# mySatellite.net
KiCad netlist of a schematic drawn in EAGLE
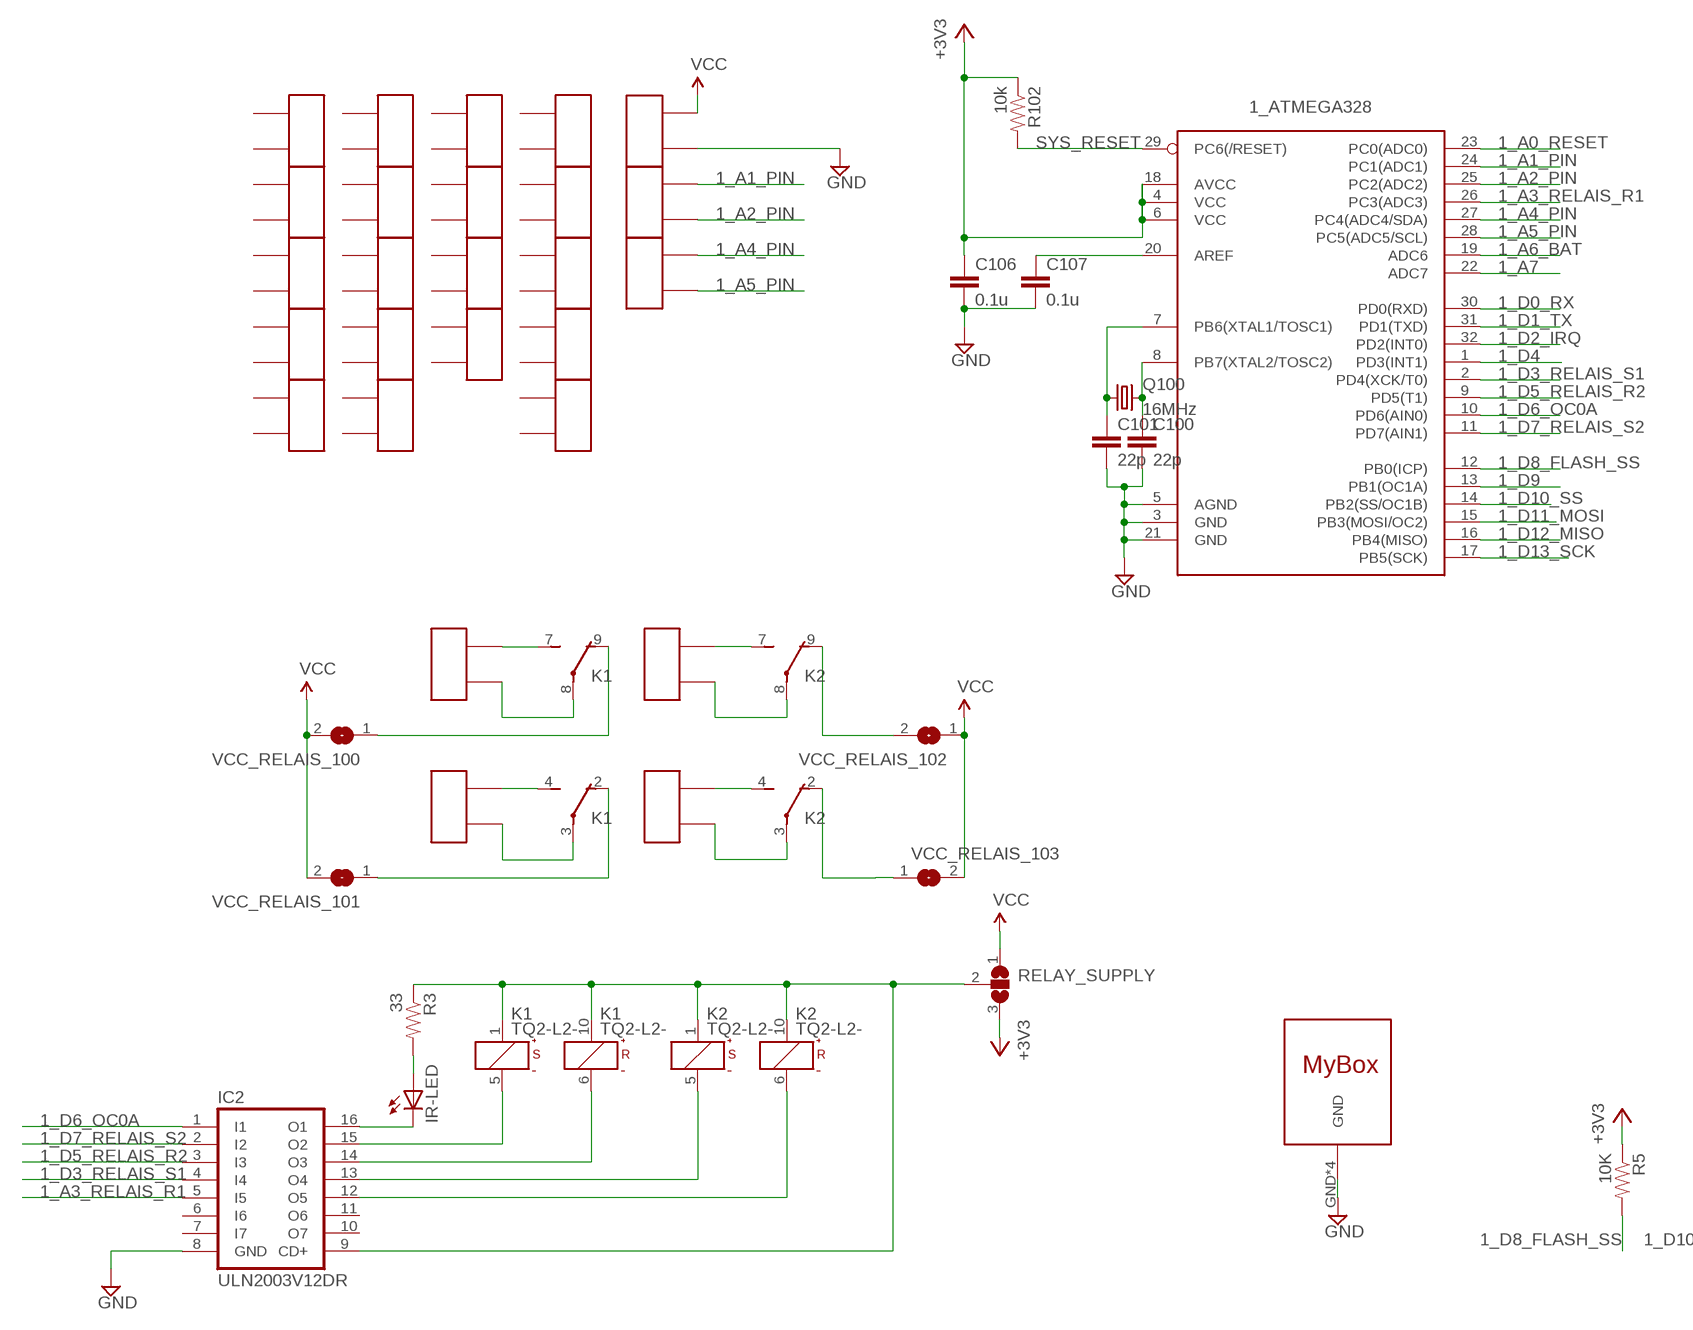
[diagram p0: schematic, sheet 1, part 1 of 2]
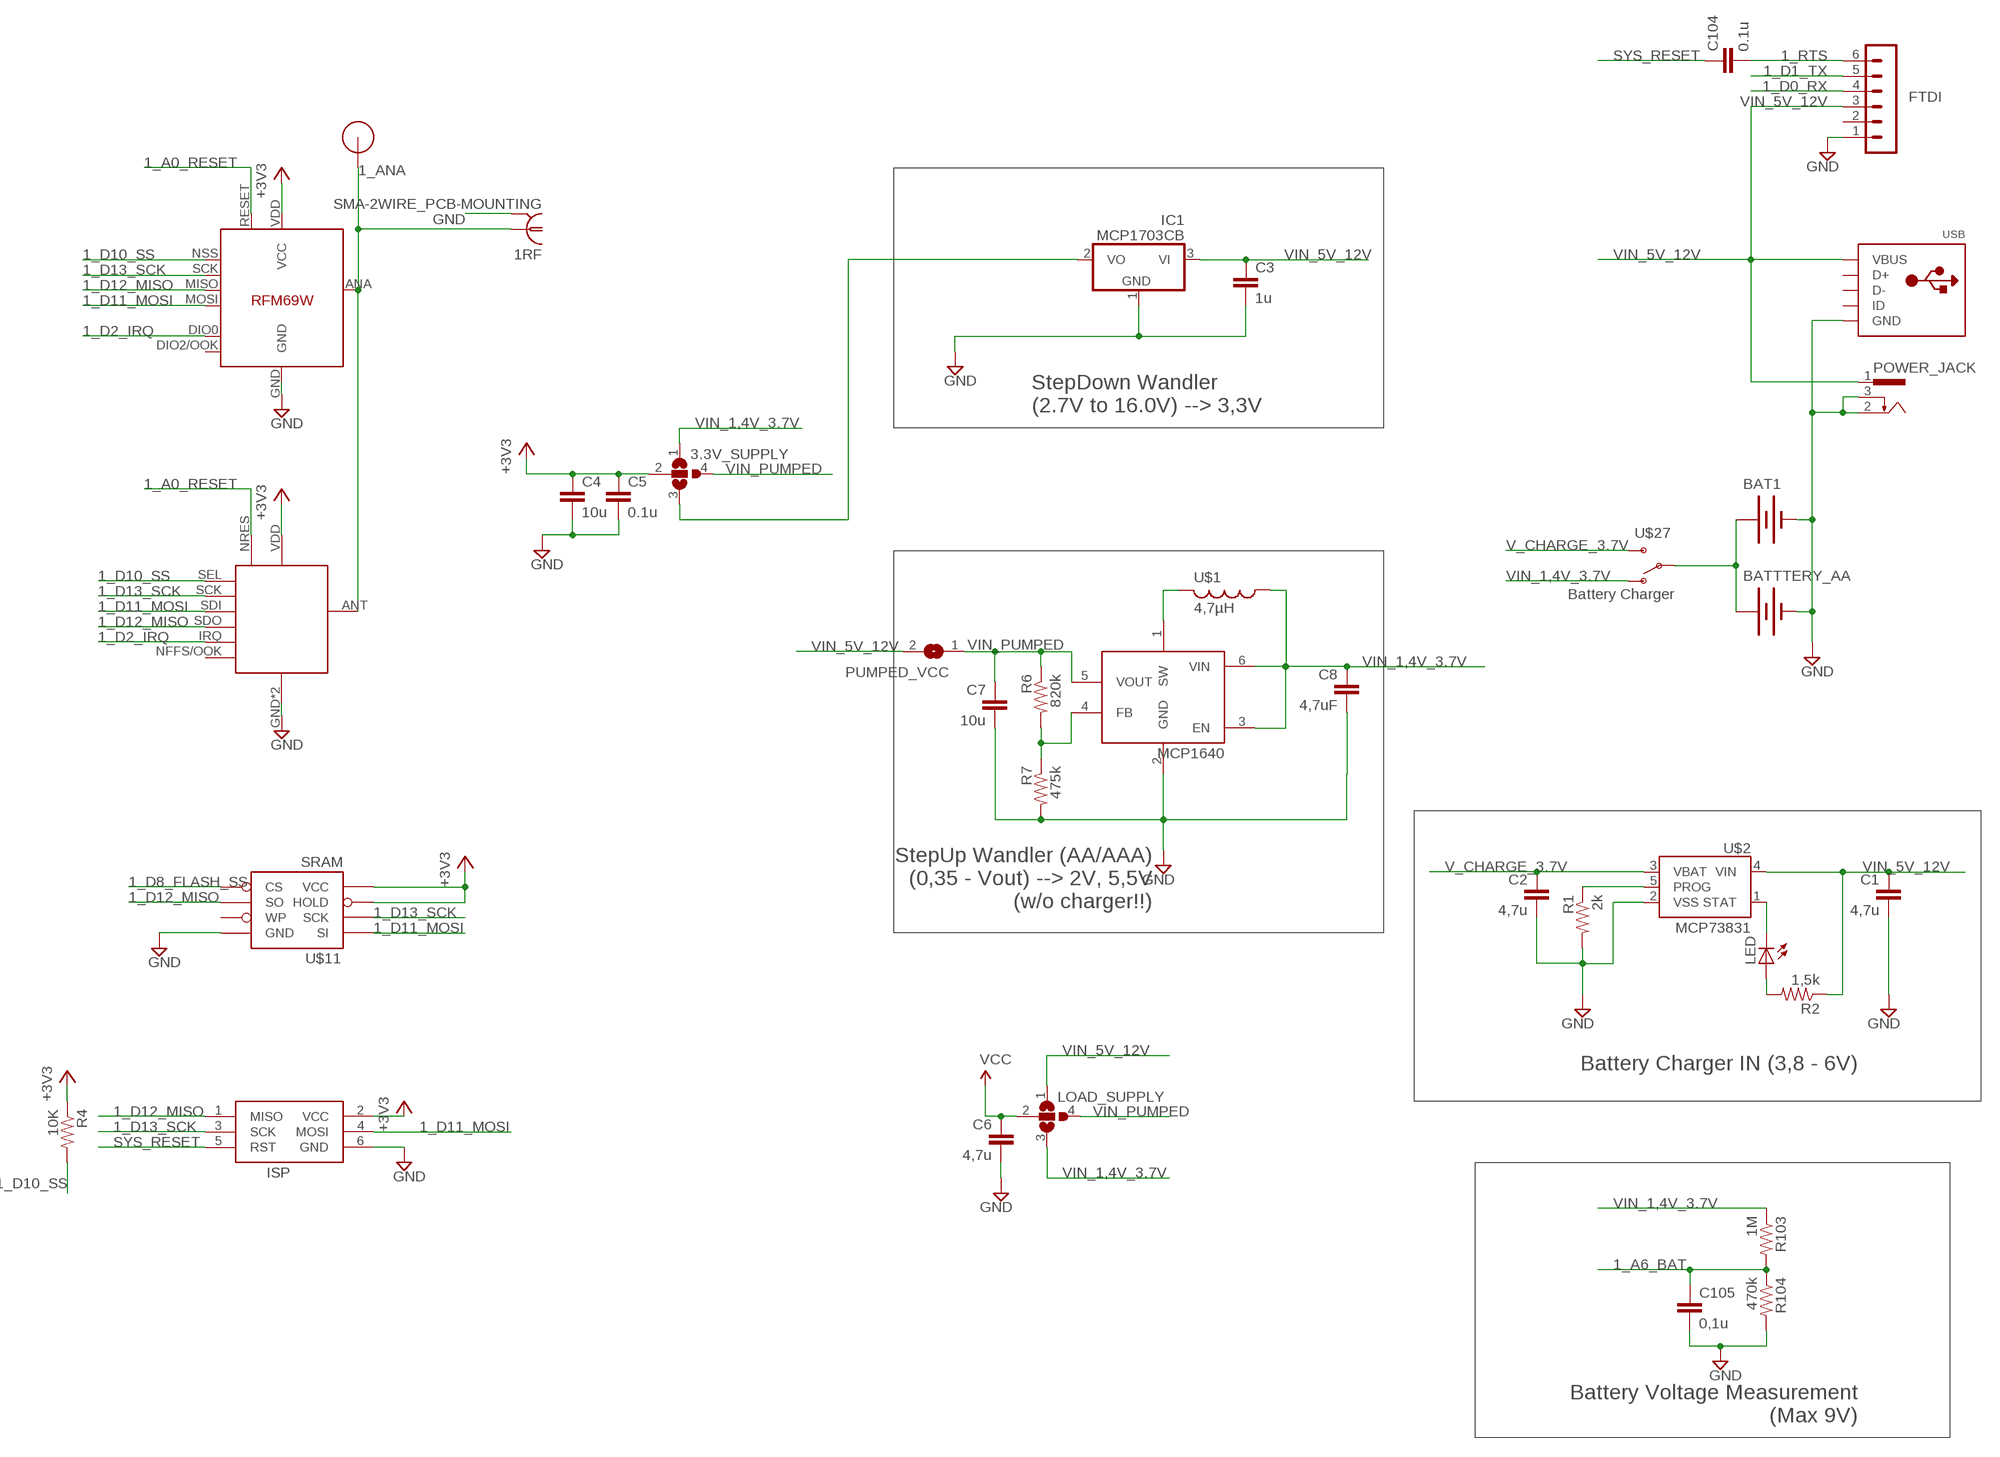
[diagram p1: schematic, sheet 1, part 2 of 2]

(export (version "E")
  (design (tool "Eeschema 10.0.6"))
  (components
    (comp (ref "1RF")
      (value "SMA-2WIRE_PCB-MOUNTING")
      (footprint "eagle-import:J01151A0931")
      (libsource (lib "eagle-import") (part "SMA-2WIRE_PCB-MOUNTING"))
    )
    (comp (ref "1_ATMEGA328")
      (value "ATMega-328")
      (footprint "eagle-import:TQFP32-08")
      (libsource (lib "eagle-import") (part "ATMEGA168/328TQFP32"))
    )
    (comp (ref "1_RFM12")
      (value "RFM12B_MINPADS")
      (footprint "eagle-import:RFM12B-MINPADS")
      (libsource (lib "eagle-import") (part "RFM12B_MINPADS"))
    )
    (comp (ref "1_RFM69")
      (value "RFM69_MINIPADS")
      (footprint "eagle-import:RFM69W-MINPADS")
      (libsource (lib "eagle-import") (part "RFM69_MINIPADS"))
    )
    (comp (ref "3.3V_SUPPLY")
      (value "SJ3W")
      (footprint "eagle-import:SJ_3")
      (libsource (lib "eagle-import") (part "SJ3W"))
    )
    (comp (ref "ADC1")
      (value "HDR_2PIN")
      (footprint "eagle-import:1X02_NS")
      (libsource (lib "eagle-import") (part "HDR_2PIN"))
    )
    (comp (ref "ADC2")
      (value "HDR_2PIN")
      (footprint "eagle-import:1X02_NS")
      (libsource (lib "eagle-import") (part "HDR_2PIN"))
    )
    (comp (ref "BAT1")
      (value "BATTERY")
      (footprint "eagle-import:BATTERY-CR2")
      (libsource (lib "eagle-import") (part "BATTERY"))
    )
    (comp (ref "BATTTERY_AA")
      (value "BATTERYAA")
      (footprint "eagle-import:BATTERY-AA")
      (libsource (lib "eagle-import") (part "BATTERYAA"))
    )
    (comp (ref "C1")
      (value "4,7u")
      (footprint "eagle-import:0603-CAP")
      (libsource (lib "eagle-import") (part "CAP0603-CAP"))
    )
    (comp (ref "C2")
      (value "4,7u")
      (footprint "eagle-import:0603-CAP")
      (libsource (lib "eagle-import") (part "CAP0603-CAP"))
    )
    (comp (ref "C3")
      (value "1u")
      (footprint "eagle-import:0603-CAP")
      (libsource (lib "eagle-import") (part "CAP0603-CAP"))
    )
    (comp (ref "C4")
      (value "10u")
      (footprint "eagle-import:0603-CAP")
      (libsource (lib "eagle-import") (part "CAP0603-CAP"))
    )
    (comp (ref "C5")
      (value "0.1u")
      (footprint "eagle-import:0603-CAP")
      (libsource (lib "eagle-import") (part "CAP0603-CAP"))
    )
    (comp (ref "C6")
      (value "4,7u")
      (footprint "eagle-import:0603-CAP")
      (libsource (lib "eagle-import") (part "CAP0603-CAP"))
    )
    (comp (ref "C7")
      (value "10u")
      (footprint "eagle-import:0603-CAP")
      (libsource (lib "eagle-import") (part "CAP0603-CAP"))
    )
    (comp (ref "C8")
      (value "4,7uF")
      (footprint "eagle-import:0603-CAP")
      (libsource (lib "eagle-import") (part "CAP0603-CAP"))
    )
    (comp (ref "C100")
      (value "22p")
      (footprint "eagle-import:0603-CAP")
      (libsource (lib "eagle-import") (part "CAP0603-CAP"))
    )
    (comp (ref "C101")
      (value "22p")
      (footprint "eagle-import:0603-CAP")
      (libsource (lib "eagle-import") (part "CAP0603-CAP"))
    )
    (comp (ref "C104")
      (value "0.1u")
      (footprint "eagle-import:0603-CAP")
      (libsource (lib "eagle-import") (part "CAP0603-CAP"))
    )
    (comp (ref "C105")
      (value "0,1u")
      (footprint "eagle-import:0603-CAP")
      (libsource (lib "eagle-import") (part "CAP0603-CAP"))
    )
    (comp (ref "C106")
      (value "0.1u")
      (footprint "eagle-import:0603-CAP")
      (libsource (lib "eagle-import") (part "CAP0603-CAP"))
    )
    (comp (ref "C107")
      (value "0.1u")
      (footprint "eagle-import:0603-CAP")
      (libsource (lib "eagle-import") (part "CAP0603-CAP"))
    )
    (comp (ref "FTDI")
      (value "FTDI")
      (footprint "eagle-import:MA06-1")
      (libsource (lib "eagle-import") (part "MA06-1"))
    )
    (comp (ref "IC1")
      (value "MCP1703CB")
      (footprint "eagle-import:SOT23")
      (libsource (lib "eagle-import") (part "MCP1703CB"))
    )
    (comp (ref "IC2")
      (value "ULN2003V12DR")
      (footprint "eagle-import:SO16")
      (libsource (lib "eagle-import") (part "ULN2003AD"))
    )
    (comp (ref "IR-LED")
      (value "LED5MM")
      (footprint "eagle-import:LED5MM")
      (libsource (lib "eagle-import") (part "led_LED5MM"))
    )
    (comp (ref "IR/RELAY_SATELLITE")
      (value "MY-BOX")
      (footprint "eagle-import:MY-BOX")
      (libsource (lib "eagle-import") (part "MY-BOX"))
    )
    (comp (ref "ISP")
      (value "AVRISP")
      (footprint "eagle-import:AVRISP-EDGE")
      (fields (field (name "BUERKLIN") "56F6228"))
      (libsource (lib "eagle-import") (part "AVRISP"))
    )
    (comp (ref "K1")
      (value "TQ2-L2-")
      (footprint "eagle-import:TQ2")
      (fields
        (field (name "MF") "AROMAT/ MATSUSHITA")
        (field (name "MPN") "TQ2-L2-9V")
        (field (name "BUERKLIN") "30 G 7570")
        (field (name "MPN_1") "TQ2-L2-3V")
      )
      (libsource (lib "eagle-import") (part "TQ2?-L2-"))
    )
    (comp (ref "K2")
      (value "TQ2-L2-")
      (footprint "eagle-import:TQ2")
      (fields
        (field (name "MF") "AROMAT/ MATSUSHITA")
        (field (name "MPN") "TQ2-L2-9V")
        (field (name "BUERKLIN") "30 G 7570")
        (field (name "MPN_1") "TQ2-L2-3V")
      )
      (libsource (lib "eagle-import") (part "TQ2?-L2-"))
    )
    (comp (ref "LED")
      (value "LED3MM")
      (footprint "eagle-import:LED3MM")
      (libsource (lib "eagle-import") (part "LED3MM"))
    )
    (comp (ref "LOAD_SUPPLY")
      (value "SJ3W")
      (footprint "eagle-import:SJ_3")
      (libsource (lib "eagle-import") (part "SJ3W"))
    )
    (comp (ref "POWER_JACK")
      (value "LUMBERG_1613-200-62")
      (footprint "eagle-import:733980-62")
      (libsource (lib "eagle-import") (part "LUMBERG_1613-200-62"))
    )
    (comp (ref "PUMPED_VCC")
      (value "SJ")
      (footprint "eagle-import:SJ")
      (libsource (lib "eagle-import") (part "SJ"))
    )
    (comp (ref "Q100")
      (value "16MHz")
      (footprint "eagle-import:HC49_S")
      (libsource (lib "eagle-import") (part "CRYSTALHC49S"))
    )
    (comp (ref "R1")
      (value "2k")
      (footprint "eagle-import:0603-RES")
      (libsource (lib "eagle-import") (part "RESISTOR0603-RES"))
    )
    (comp (ref "R2")
      (value "1,5k")
      (footprint "eagle-import:0603-RES")
      (libsource (lib "eagle-import") (part "RESISTOR0603-RES"))
    )
    (comp (ref "R3")
      (value "33")
      (footprint "eagle-import:0603-RES")
      (libsource (lib "eagle-import") (part "RESISTOR0603-RES"))
    )
    (comp (ref "R4")
      (value "10K")
      (footprint "eagle-import:0603-RES")
      (libsource (lib "eagle-import") (part "RESISTOR0603-RES"))
    )
    (comp (ref "R5")
      (value "10K")
      (footprint "eagle-import:0603-RES")
      (libsource (lib "eagle-import") (part "RESISTOR0603-RES"))
    )
    (comp (ref "R6")
      (value "820k")
      (footprint "eagle-import:0603-RES")
      (libsource (lib "eagle-import") (part "RESISTOR0603-RES"))
    )
    (comp (ref "R7")
      (value "475k")
      (footprint "eagle-import:0603-RES")
      (libsource (lib "eagle-import") (part "RESISTOR0603-RES"))
    )
    (comp (ref "R102")
      (value "10k")
      (footprint "eagle-import:0603-RES")
      (libsource (lib "eagle-import") (part "RESISTOR0603-RES"))
    )
    (comp (ref "R103")
      (value "1M")
      (footprint "eagle-import:0603-RES")
      (libsource (lib "eagle-import") (part "RESISTOR0603-RES"))
    )
    (comp (ref "R104")
      (value "470k")
      (footprint "eagle-import:0603-RES")
      (libsource (lib "eagle-import") (part "RESISTOR0603-RES"))
    )
    (comp (ref "RELAY_SUPPLY")
      (value "SJ2W")
      (footprint "eagle-import:SJ_2")
      (libsource (lib "eagle-import") (part "SJ2W"))
    )
    (comp (ref "U$1")
      (value "4,7µH")
      (footprint "eagle-import:INDUCTOR_EPCOS")
      (libsource (lib "eagle-import") (part "INDUCTOR_B82462G"))
    )
    (comp (ref "U$2")
      (value "MCP73831")
      (footprint "eagle-import:SOT23-5")
      (libsource (lib "eagle-import") (part "MCP73831"))
    )
    (comp (ref "U$3")
      (value "HDR_2PIN")
      (footprint "eagle-import:1X02_NS")
      (libsource (lib "eagle-import") (part "HDR_2PIN"))
    )
    (comp (ref "U$5")
      (value "HDR_2PIN")
      (footprint "eagle-import:1X02_NS")
      (libsource (lib "eagle-import") (part "HDR_2PIN"))
    )
    (comp (ref "U$6")
      (value "HDR_2PIN")
      (footprint "eagle-import:1X02_NS")
      (libsource (lib "eagle-import") (part "HDR_2PIN"))
    )
    (comp (ref "U$7")
      (value "HDR_2PIN")
      (footprint "eagle-import:1X02_NS")
      (libsource (lib "eagle-import") (part "HDR_2PIN"))
    )
    (comp (ref "U$8")
      (value "HDR_2PIN")
      (footprint "eagle-import:1X02_NS")
      (libsource (lib "eagle-import") (part "HDR_2PIN"))
    )
    (comp (ref "U$9")
      (value "HDR_2PIN")
      (footprint "eagle-import:1X02_NS")
      (libsource (lib "eagle-import") (part "HDR_2PIN"))
    )
    (comp (ref "U$10")
      (value "HDR_2PIN")
      (footprint "eagle-import:1X02_NS")
      (libsource (lib "eagle-import") (part "HDR_2PIN"))
    )
    (comp (ref "U$11")
      (value "SRAM")
      (footprint "eagle-import:LOWPOWERLAB_SO08")
      (libsource (lib "eagle-import") (part "SRAM_32K256JEDEC_3.9MM"))
    )
    (comp (ref "U$12")
      (value "HDR_2PIN")
      (footprint "eagle-import:1X02_NS")
      (libsource (lib "eagle-import") (part "HDR_2PIN"))
    )
    (comp (ref "U$13")
      (value "HDR_2PIN")
      (footprint "eagle-import:1X02_NS")
      (libsource (lib "eagle-import") (part "HDR_2PIN"))
    )
    (comp (ref "U$14")
      (value "HDR_2PIN")
      (footprint "eagle-import:1X02_NS")
      (libsource (lib "eagle-import") (part "HDR_2PIN"))
    )
    (comp (ref "U$15")
      (value "HDR_2PIN")
      (footprint "eagle-import:1X02_NS")
      (libsource (lib "eagle-import") (part "HDR_2PIN"))
    )
    (comp (ref "U$16")
      (value "HDR_2PIN")
      (footprint "eagle-import:1X02_NS")
      (libsource (lib "eagle-import") (part "HDR_2PIN"))
    )
    (comp (ref "U$17")
      (value "HDR_2PIN")
      (footprint "eagle-import:1X02_NS")
      (libsource (lib "eagle-import") (part "HDR_2PIN"))
    )
    (comp (ref "U$18")
      (value "RFM12B_ANTENNA")
      (footprint "eagle-import:RFM12B-ANTENNA")
      (libsource (lib "eagle-import") (part "RFM12B_ANTENNA"))
    )
    (comp (ref "U$19")
      (value "HDR_2PIN")
      (footprint "eagle-import:1X02_NS")
      (libsource (lib "eagle-import") (part "HDR_2PIN"))
    )
    (comp (ref "U$20")
      (value "HDR_2PIN")
      (footprint "eagle-import:1X02_NS")
      (libsource (lib "eagle-import") (part "HDR_2PIN"))
    )
    (comp (ref "U$21")
      (value "HDR_2PIN")
      (footprint "eagle-import:1X02_NS")
      (libsource (lib "eagle-import") (part "HDR_2PIN"))
    )
    (comp (ref "U$22")
      (value "HDR_2PIN")
      (footprint "eagle-import:1X02_NS")
      (libsource (lib "eagle-import") (part "HDR_2PIN"))
    )
    (comp (ref "U$23")
      (value "HDR_2PIN")
      (footprint "eagle-import:1X02_NS")
      (libsource (lib "eagle-import") (part "HDR_2PIN"))
    )
    (comp (ref "U$24")
      (value "HDR_2PIN")
      (footprint "eagle-import:1X02_NS")
      (libsource (lib "eagle-import") (part "HDR_2PIN"))
    )
    (comp (ref "U$25")
      (value "HDR_2PIN")
      (footprint "eagle-import:1X02_NS")
      (libsource (lib "eagle-import") (part "HDR_2PIN"))
    )
    (comp (ref "U$26")
      (value "HDR_2PIN")
      (footprint "eagle-import:1X02_NS")
      (libsource (lib "eagle-import") (part "HDR_2PIN"))
    )
    (comp (ref "U$27")
      (value "Battery Charger")
      (footprint "eagle-import:SSK-1202")
      (libsource (lib "eagle-import") (part "SLIDE_SWITCH"))
    )
    (comp (ref "U$29")
      (value "HDR_2PIN")
      (footprint "eagle-import:1X02_NS")
      (libsource (lib "eagle-import") (part "HDR_2PIN"))
    )
    (comp (ref "U$30")
      (value "HDR_2PIN")
      (footprint "eagle-import:1X02_NS")
      (libsource (lib "eagle-import") (part "HDR_2PIN"))
    )
    (comp (ref "U1")
      (value "MCP1640")
      (footprint "eagle-import:SOT23-6")
      (libsource (lib "eagle-import") (part "MCP1640"))
    )
    (comp (ref "USB")
      (value "USBMINIB")
      (footprint "eagle-import:USB-MINIB")
      (libsource (lib "eagle-import") (part "USBMINIB"))
    )
    (comp (ref "VCC")
      (value "HDR_2PIN")
      (footprint "eagle-import:1X02_NS")
      (libsource (lib "eagle-import") (part "HDR_2PIN"))
    )
    (comp (ref "VCC_RELAIS_100")
      (value "SJ")
      (footprint "eagle-import:SJ")
      (libsource (lib "eagle-import") (part "SJ"))
    )
    (comp (ref "VCC_RELAIS_101")
      (value "SJ")
      (footprint "eagle-import:SJ")
      (libsource (lib "eagle-import") (part "SJ"))
    )
    (comp (ref "VCC_RELAIS_102")
      (value "SJ")
      (footprint "eagle-import:SJ")
      (libsource (lib "eagle-import") (part "SJ"))
    )
    (comp (ref "VCC_RELAIS_103")
      (value "SJ")
      (footprint "eagle-import:SJ")
      (libsource (lib "eagle-import") (part "SJ"))
    )
  )
  (nets
    (net (code "1") (name "+3V3") (class "Default")
      (node (ref "1_ATMEGA328") (pin "18") (pinfunction "AVCC_18") (pintype "bidirectional"))
      (node (ref "1_ATMEGA328") (pin "4") (pinfunction "VCC_4") (pintype "bidirectional"))
      (node (ref "1_ATMEGA328") (pin "6") (pinfunction "VCC_6") (pintype "bidirectional"))
      (node (ref "1_RFM12") (pin "VDD") (pinfunction "VDD_VDD") (pintype "bidirectional"))
      (node (ref "1_RFM69") (pin "VDD") (pinfunction "VCC_VDD") (pintype "power_in"))
      (node (ref "3.3V_SUPPLY") (pin "2") (pinfunction "2_2") (pintype "passive"))
      (node (ref "C106") (pin "1") (pinfunction "1_1") (pintype "passive"))
      (node (ref "C4") (pin "1") (pinfunction "1_1") (pintype "passive"))
      (node (ref "C5") (pin "1") (pinfunction "1_1") (pintype "passive"))
      (node (ref "ISP") (pin "2") (pinfunction "VCC_2") (pintype "power_in"))
      (node (ref "R102") (pin "1") (pinfunction "1_1") (pintype "passive"))
      (node (ref "R4") (pin "1") (pinfunction "1_1") (pintype "passive"))
      (node (ref "R5") (pin "1") (pinfunction "1_1") (pintype "passive"))
      (node (ref "RELAY_SUPPLY") (pin "3") (pinfunction "3_3") (pintype "passive"))
      (node (ref "U$11") (pin "7_HOLD") (pinfunction "HOLD_7_HOLD") (pintype "bidirectional"))
      (node (ref "U$11") (pin "8_VCC") (pinfunction "VCC_8_VCC") (pintype "bidirectional"))
    )
    (net (code "2") (name "/1_A0_RESET") (class "Default")
      (node (ref "1_ATMEGA328") (pin "23") (pinfunction "PC0(ADC0)_23") (pintype "bidirectional"))
      (node (ref "1_RFM12") (pin "NRES") (pinfunction "NRES_NRES") (pintype "bidirectional"))
      (node (ref "1_RFM69") (pin "RESET") (pinfunction "RESET_RESET") (pintype "input"))
    )
    (net (code "3") (name "/1_A1_PIN") (class "Default")
      (node (ref "1_ATMEGA328") (pin "24") (pinfunction "PC1(ADC1)_24") (pintype "bidirectional"))
      (node (ref "ADC1") (pin "1") (pinfunction "P$1_1") (pintype "bidirectional"))
    )
    (net (code "4") (name "/1_A2_PIN") (class "Default")
      (node (ref "1_ATMEGA328") (pin "25") (pinfunction "PC2(ADC2)_25") (pintype "bidirectional"))
      (node (ref "ADC1") (pin "2") (pinfunction "P$2_2") (pintype "bidirectional"))
    )
    (net (code "5") (name "/1_A3_RELAIS_R1") (class "Default")
      (node (ref "1_ATMEGA328") (pin "26") (pinfunction "PC3(ADC3)_26") (pintype "bidirectional"))
      (node (ref "IC2") (pin "5") (pinfunction "I5_5") (pintype "input"))
    )
    (net (code "6") (name "/1_A4_PIN") (class "Default")
      (node (ref "1_ATMEGA328") (pin "27") (pinfunction "PC4(ADC4/SDA)_27") (pintype "bidirectional"))
      (node (ref "ADC2") (pin "1") (pinfunction "P$1_1") (pintype "bidirectional"))
    )
    (net (code "7") (name "/1_A5_PIN") (class "Default")
      (node (ref "1_ATMEGA328") (pin "28") (pinfunction "PC5(ADC5/SCL)_28") (pintype "bidirectional"))
      (node (ref "ADC2") (pin "2") (pinfunction "P$2_2") (pintype "bidirectional"))
    )
    (net (code "8") (name "/1_A6_BAT") (class "Default")
      (node (ref "1_ATMEGA328") (pin "19") (pinfunction "ADC6_19") (pintype "bidirectional"))
      (node (ref "C105") (pin "1") (pinfunction "1_1") (pintype "passive"))
      (node (ref "R103") (pin "2") (pinfunction "2_2") (pintype "passive"))
      (node (ref "R104") (pin "1") (pinfunction "1_1") (pintype "passive"))
    )
    (net (code "9") (name "/1_A7") (class "Default")
      (node (ref "1_ATMEGA328") (pin "22") (pinfunction "ADC7_22") (pintype "bidirectional"))
    )
    (net (code "10") (name "/1_ANA") (class "Default")
      (node (ref "1RF") (pin "1") (pinfunction "1_1") (pintype "passive"))
      (node (ref "1_RFM12") (pin "ANT") (pinfunction "ANT_ANT") (pintype "bidirectional"))
      (node (ref "1_RFM69") (pin "ANA") (pinfunction "ANT_ANA") (pintype "passive"))
      (node (ref "U$18") (pin "P$1") (pinfunction "1_P$1") (pintype "bidirectional"))
    )
    (net (code "11") (name "/1_D0_RX") (class "Default")
      (node (ref "1_ATMEGA328") (pin "30") (pinfunction "PD0(RXD)_30") (pintype "bidirectional"))
      (node (ref "FTDI") (pin "4") (pinfunction "4_4") (pintype "passive"))
    )
    (net (code "12") (name "/1_D1_TX") (class "Default")
      (node (ref "1_ATMEGA328") (pin "31") (pinfunction "PD1(TXD)_31") (pintype "bidirectional"))
      (node (ref "FTDI") (pin "5") (pinfunction "5_5") (pintype "passive"))
    )
    (net (code "13") (name "/1_D2_IRQ") (class "Default")
      (node (ref "1_ATMEGA328") (pin "32") (pinfunction "PD2(INT0)_32") (pintype "bidirectional"))
      (node (ref "1_RFM12") (pin "IRQ") (pinfunction "IRQ_IRQ") (pintype "bidirectional"))
      (node (ref "1_RFM69") (pin "DIO0") (pinfunction "DIO0/IRQ_DIO0") (pintype "open_collector"))
    )
    (net (code "14") (name "/1_D3_RELAIS_S1") (class "Default")
      (node (ref "1_ATMEGA328") (pin "2") (pinfunction "PD4(XCK/T0)_2") (pintype "bidirectional"))
      (node (ref "IC2") (pin "4") (pinfunction "I4_4") (pintype "input"))
    )
    (net (code "15") (name "/1_D4") (class "Default")
      (node (ref "1_ATMEGA328") (pin "1") (pinfunction "PD3(INT1)_1") (pintype "bidirectional"))
    )
    (net (code "16") (name "/1_D5_RELAIS_R2") (class "Default")
      (node (ref "1_ATMEGA328") (pin "9") (pinfunction "PD5(T1)_9") (pintype "bidirectional"))
      (node (ref "IC2") (pin "3") (pinfunction "I3_3") (pintype "input"))
    )
    (net (code "17") (name "/1_D6_OC0A") (class "Default")
      (node (ref "1_ATMEGA328") (pin "10") (pinfunction "PD6(AIN0)_10") (pintype "bidirectional"))
      (node (ref "IC2") (pin "1") (pinfunction "I1_1") (pintype "input"))
    )
    (net (code "18") (name "/1_D7_RELAIS_S2") (class "Default")
      (node (ref "1_ATMEGA328") (pin "11") (pinfunction "PD7(AIN1)_11") (pintype "bidirectional"))
      (node (ref "IC2") (pin "2") (pinfunction "I2_2") (pintype "input"))
    )
    (net (code "19") (name "/1_D8_FLASH_SS") (class "Default")
      (node (ref "1_ATMEGA328") (pin "12") (pinfunction "PB0(ICP)_12") (pintype "bidirectional"))
      (node (ref "R5") (pin "2") (pinfunction "2_2") (pintype "passive"))
      (node (ref "U$11") (pin "1_CS") (pinfunction "CS_1_CS") (pintype "bidirectional"))
    )
    (net (code "20") (name "/1_D9") (class "Default")
      (node (ref "1_ATMEGA328") (pin "13") (pinfunction "PB1(OC1A)_13") (pintype "bidirectional"))
    )
    (net (code "21") (name "/1_D10_SS") (class "Default")
      (node (ref "1_ATMEGA328") (pin "14") (pinfunction "PB2(SS/OC1B)_14") (pintype "bidirectional"))
      (node (ref "1_RFM12") (pin "SEL") (pinfunction "SEL_SEL") (pintype "bidirectional"))
      (node (ref "1_RFM69") (pin "NSS") (pinfunction "SEL_NSS") (pintype "input"))
      (node (ref "R4") (pin "2") (pinfunction "2_2") (pintype "passive"))
    )
    (net (code "22") (name "/1_D11_MOSI") (class "Default")
      (node (ref "1_ATMEGA328") (pin "15") (pinfunction "PB3(MOSI/OC2)_15") (pintype "bidirectional"))
      (node (ref "1_RFM12") (pin "SDI") (pinfunction "SDI/MOSI_SDI") (pintype "bidirectional"))
      (node (ref "1_RFM69") (pin "MOSI") (pinfunction "MOSI_MOSI") (pintype "output"))
      (node (ref "ISP") (pin "4") (pinfunction "MOSI_4") (pintype "output"))
      (node (ref "U$11") (pin "5_SI") (pinfunction "SI_5_SI") (pintype "bidirectional"))
    )
    (net (code "23") (name "/1_D12_MISO") (class "Default")
      (node (ref "1_ATMEGA328") (pin "16") (pinfunction "PB4(MISO)_16") (pintype "bidirectional"))
      (node (ref "1_RFM12") (pin "SDO") (pinfunction "SDO/MISO_SDO") (pintype "bidirectional"))
      (node (ref "1_RFM69") (pin "MISO") (pinfunction "MISO_MISO") (pintype "input"))
      (node (ref "ISP") (pin "1") (pinfunction "MISO_1") (pintype "input"))
      (node (ref "U$11") (pin "2_SO") (pinfunction "SO_2_SO") (pintype "bidirectional"))
    )
    (net (code "24") (name "/1_D13_SCK") (class "Default")
      (node (ref "1_ATMEGA328") (pin "17") (pinfunction "PB5(SCK)_17") (pintype "bidirectional"))
      (node (ref "1_RFM12") (pin "SCK") (pinfunction "SCK_SCK") (pintype "bidirectional"))
      (node (ref "1_RFM69") (pin "SCK") (pinfunction "SCK_SCK") (pintype "input"))
      (node (ref "ISP") (pin "3") (pinfunction "SCK_3") (pintype "output"))
      (node (ref "U$11") (pin "6_SCK") (pinfunction "SCK_6_SCK") (pintype "bidirectional"))
    )
    (net (code "25") (name "/1_RTS") (class "Default")
      (node (ref "C104") (pin "2") (pinfunction "2_2") (pintype "passive"))
      (node (ref "FTDI") (pin "6") (pinfunction "6_6") (pintype "passive"))
    )
    (net (code "26") (name "/SYS_RESET") (class "Default")
      (node (ref "1_ATMEGA328") (pin "29") (pinfunction "PC6(/RESET)_29") (pintype "bidirectional"))
      (node (ref "C104") (pin "1") (pinfunction "1_1") (pintype "passive"))
      (node (ref "ISP") (pin "5") (pinfunction "RST_5") (pintype "output"))
      (node (ref "R102") (pin "2") (pinfunction "2_2") (pintype "passive"))
    )
    (net (code "27") (name "/VIN_1,4V_3.7V") (class "Default")
      (node (ref "3.3V_SUPPLY") (pin "1") (pinfunction "1_1") (pintype "passive"))
      (node (ref "C8") (pin "1") (pinfunction "1_1") (pintype "passive"))
      (node (ref "LOAD_SUPPLY") (pin "3") (pinfunction "3_3") (pintype "passive"))
      (node (ref "R103") (pin "1") (pinfunction "1_1") (pintype "passive"))
      (node (ref "U$1") (pin "P$1") (pinfunction "1_P$1") (pintype "passive"))
      (node (ref "U$27") (pin "O") (pinfunction "O_O") (pintype "passive"))
      (node (ref "U1") (pin "3") (pinfunction "EN_3") (pintype "input"))
      (node (ref "U1") (pin "6") (pinfunction "VIN_6") (pintype "input"))
    )
    (net (code "28") (name "/VIN_5V_12V") (class "Default")
      (node (ref "C1") (pin "1") (pinfunction "1_1") (pintype "passive"))
      (node (ref "C3") (pin "1") (pinfunction "1_1") (pintype "passive"))
      (node (ref "FTDI") (pin "3") (pinfunction "3_3") (pintype "passive"))
      (node (ref "IC1") (pin "3") (pinfunction "VI_3") (pintype "input"))
      (node (ref "LOAD_SUPPLY") (pin "1") (pinfunction "1_1") (pintype "passive"))
      (node (ref "POWER_JACK") (pin "1") (pinfunction "1_1") (pintype "passive"))
      (node (ref "PUMPED_VCC") (pin "2") (pinfunction "2_2") (pintype "passive"))
      (node (ref "R2") (pin "1") (pinfunction "1_1") (pintype "passive"))
      (node (ref "U$2") (pin "4") (pinfunction "VIN_4") (pintype "power_in"))
      (node (ref "USB") (pin "VBUS") (pinfunction "VBUS_VBUS") (pintype "power_in"))
    )
    (net (code "29") (name "/VIN_PUMPED") (class "Default")
      (node (ref "3.3V_SUPPLY") (pin "4") (pinfunction "4_4") (pintype "passive"))
      (node (ref "C7") (pin "1") (pinfunction "1_1") (pintype "passive"))
      (node (ref "LOAD_SUPPLY") (pin "4") (pinfunction "4_4") (pintype "passive"))
      (node (ref "PUMPED_VCC") (pin "1") (pinfunction "1_1") (pintype "passive"))
      (node (ref "R6") (pin "1") (pinfunction "1_1") (pintype "passive"))
      (node (ref "U1") (pin "5") (pinfunction "VOUT_5") (pintype "output"))
    )
    (net (code "30") (name "/V_CHARGE_3.7V") (class "Default")
      (node (ref "C2") (pin "1") (pinfunction "1_1") (pintype "passive"))
      (node (ref "U$2") (pin "3") (pinfunction "VBAT_3") (pintype "power_in"))
      (node (ref "U$27") (pin "S") (pinfunction "S_S") (pintype "passive"))
    )
    (net (code "31") (name "GND") (class "Default")
      (node (ref "1RF") (pin "G@1") (pinfunction "2_G@1") (pintype "passive"))
      (node (ref "1RF") (pin "G@2") (pinfunction "2_G@2") (pintype "passive"))
      (node (ref "1RF") (pin "G@3") (pinfunction "2_G@3") (pintype "passive"))
      (node (ref "1RF") (pin "G@4") (pinfunction "2_G@4") (pintype "passive"))
      (node (ref "1_ATMEGA328") (pin "21") (pinfunction "GND_21") (pintype "bidirectional"))
      (node (ref "1_ATMEGA328") (pin "3") (pinfunction "GND_3") (pintype "bidirectional"))
      (node (ref "1_ATMEGA328") (pin "5") (pinfunction "AGND_5") (pintype "bidirectional"))
      (node (ref "1_RFM12") (pin "GND") (pinfunction "GND_GND") (pintype "bidirectional"))
      (node (ref "1_RFM12") (pin "GND1") (pinfunction "GND_GND1") (pintype "bidirectional"))
      (node (ref "1_RFM69") (pin "GND") (pinfunction "GND_GND") (pintype "power_in"))
      (node (ref "BAT1") (pin "GND@1") (pinfunction "-_GND@1") (pintype "power_in"))
      (node (ref "BATTTERY_AA") (pin "GND@1") (pinfunction "-_GND@1") (pintype "power_in"))
      (node (ref "C1") (pin "2") (pinfunction "2_2") (pintype "passive"))
      (node (ref "C100") (pin "2") (pinfunction "2_2") (pintype "passive"))
      (node (ref "C101") (pin "2") (pinfunction "2_2") (pintype "passive"))
      (node (ref "C105") (pin "2") (pinfunction "2_2") (pintype "passive"))
      (node (ref "C106") (pin "2") (pinfunction "2_2") (pintype "passive"))
      (node (ref "C107") (pin "2") (pinfunction "2_2") (pintype "passive"))
      (node (ref "C2") (pin "2") (pinfunction "2_2") (pintype "passive"))
      (node (ref "C3") (pin "2") (pinfunction "2_2") (pintype "passive"))
      (node (ref "C4") (pin "2") (pinfunction "2_2") (pintype "passive"))
      (node (ref "C5") (pin "2") (pinfunction "2_2") (pintype "passive"))
      (node (ref "C6") (pin "2") (pinfunction "2_2") (pintype "passive"))
      (node (ref "C7") (pin "2") (pinfunction "2_2") (pintype "passive"))
      (node (ref "C8") (pin "2") (pinfunction "2_2") (pintype "passive"))
      (node (ref "FTDI") (pin "1") (pinfunction "1_1") (pintype "passive"))
      (node (ref "IC1") (pin "1") (pinfunction "GND_1") (pintype "passive"))
      (node (ref "IC2") (pin "8") (pinfunction "GND_8") (pintype "power_in"))
      (node (ref "IR/RELAY_SATELLITE") (pin "GND") (pinfunction "GND_GND") (pintype "bidirectional"))
      (node (ref "IR/RELAY_SATELLITE") (pin "GND1") (pinfunction "GND_GND1") (pintype "bidirectional"))
      (node (ref "IR/RELAY_SATELLITE") (pin "GND2") (pinfunction "GND_GND2") (pintype "bidirectional"))
      (node (ref "IR/RELAY_SATELLITE") (pin "GND3") (pinfunction "GND_GND3") (pintype "bidirectional"))
      (node (ref "ISP") (pin "6") (pinfunction "GND_6") (pintype "power_in"))
      (node (ref "POWER_JACK") (pin "2") (pinfunction "2_2") (pintype "passive"))
      (node (ref "POWER_JACK") (pin "3") (pinfunction "3_3") (pintype "passive"))
      (node (ref "R1") (pin "2") (pinfunction "2_2") (pintype "passive"))
      (node (ref "R104") (pin "2") (pinfunction "2_2") (pintype "passive"))
      (node (ref "R7") (pin "2") (pinfunction "2_2") (pintype "passive"))
      (node (ref "U$11") (pin "4_GND") (pinfunction "GND_4_GND") (pintype "bidirectional"))
      (node (ref "U$2") (pin "2") (pinfunction "VSS_2") (pintype "power_in"))
      (node (ref "U1") (pin "2") (pinfunction "GND_2") (pintype "power_in"))
      (node (ref "USB") (pin "GND") (pinfunction "GND_GND") (pintype "power_in"))
      (node (ref "VCC") (pin "2") (pinfunction "P$2_2") (pintype "bidirectional"))
    )
    (net (code "32") (name "Net-(1_ATMEGA328-AREF)") (class "Default")
      (node (ref "1_ATMEGA328") (pin "20") (pinfunction "AREF_20") (pintype "bidirectional"))
      (node (ref "C107") (pin "1") (pinfunction "1_1") (pintype "passive"))
    )
    (net (code "33") (name "Net-(1_ATMEGA328-PB6(XTAL1{slash}TOSC1))") (class "Default")
      (node (ref "1_ATMEGA328") (pin "7") (pinfunction "PB6(XTAL1/TOSC1)_7") (pintype "bidirectional"))
      (node (ref "C101") (pin "1") (pinfunction "1_1") (pintype "passive"))
      (node (ref "Q100") (pin "1") (pinfunction "1_1") (pintype "passive"))
    )
    (net (code "34") (name "Net-(1_ATMEGA328-PB7(XTAL2{slash}TOSC2))") (class "Default")
      (node (ref "1_ATMEGA328") (pin "8") (pinfunction "PB7(XTAL2/TOSC2)_8") (pintype "bidirectional"))
      (node (ref "C100") (pin "1") (pinfunction "1_1") (pintype "passive"))
      (node (ref "Q100") (pin "2") (pinfunction "2_2") (pintype "passive"))
    )
    (net (code "35") (name "Net-(BAT1-+)") (class "Default")
      (node (ref "BAT1") (pin "PWR@1") (pinfunction "+_PWR@1") (pintype "power_in"))
      (node (ref "BATTTERY_AA") (pin "PWR@1") (pinfunction "+_PWR@1") (pintype "power_in"))
      (node (ref "U$27") (pin "P") (pinfunction "P_P") (pintype "passive"))
    )
    (net (code "36") (name "Net-(IC1-VO)") (class "Default")
      (node (ref "3.3V_SUPPLY") (pin "3") (pinfunction "3_3") (pintype "passive"))
      (node (ref "IC1") (pin "2") (pinfunction "VO_2") (pintype "passive"))
    )
    (net (code "37") (name "Net-(IC2-CD+)") (class "Default")
      (node (ref "IC2") (pin "9") (pinfunction "CD+_9") (pintype "passive"))
      (node (ref "K1") (pin "1") (pinfunction "+_1") (pintype "passive"))
      (node (ref "K1") (pin "10") (pinfunction "+_10") (pintype "passive"))
      (node (ref "K2") (pin "1") (pinfunction "+_1") (pintype "passive"))
      (node (ref "K2") (pin "10") (pinfunction "+_10") (pintype "passive"))
      (node (ref "R3") (pin "1") (pinfunction "1_1") (pintype "passive"))
      (node (ref "RELAY_SUPPLY") (pin "2") (pinfunction "2_2") (pintype "passive"))
    )
    (net (code "38") (name "Net-(IC2-O1)") (class "Default")
      (node (ref "IC2") (pin "16") (pinfunction "O1_16") (pintype "open_collector"))
      (node (ref "IR-LED") (pin "K") (pinfunction "C_K") (pintype "passive"))
    )
    (net (code "39") (name "Net-(IC2-O2)") (class "Default")
      (node (ref "IC2") (pin "15") (pinfunction "O2_15") (pintype "open_collector"))
      (node (ref "K1") (pin "5") (pinfunction "-_5") (pintype "passive"))
    )
    (net (code "40") (name "Net-(IC2-O3)") (class "Default")
      (node (ref "IC2") (pin "14") (pinfunction "O3_14") (pintype "open_collector"))
      (node (ref "K1") (pin "6") (pinfunction "-_6") (pintype "passive"))
    )
    (net (code "41") (name "Net-(IC2-O4)") (class "Default")
      (node (ref "IC2") (pin "13") (pinfunction "O4_13") (pintype "open_collector"))
      (node (ref "K2") (pin "5") (pinfunction "-_5") (pintype "passive"))
    )
    (net (code "42") (name "Net-(IC2-O5)") (class "Default")
      (node (ref "IC2") (pin "12") (pinfunction "O5_12") (pintype "open_collector"))
      (node (ref "K2") (pin "6") (pinfunction "-_6") (pintype "passive"))
    )
    (net (code "43") (name "Net-(IR-LED-PadA)") (class "Default")
      (node (ref "IR-LED") (pin "A") (pinfunction "A_A") (pintype "passive"))
      (node (ref "R3") (pin "2") (pinfunction "2_2") (pintype "passive"))
    )
    (net (code "44") (name "Net-(K1A-O)") (class "Default")
      (node (ref "K1") (pin "2") (pinfunction "O_2") (pintype "passive"))
      (node (ref "VCC_RELAIS_101") (pin "1") (pinfunction "1_1") (pintype "passive"))
    )
    (net (code "45") (name "Net-(K1A-P)") (class "Default")
      (node (ref "K1") (pin "3") (pinfunction "P_3") (pintype "passive"))
      (node (ref "U$22") (pin "1") (pinfunction "P$1_1") (pintype "bidirectional"))
    )
    (net (code "46") (name "Net-(K1A-S)") (class "Default")
      (node (ref "K1") (pin "4") (pinfunction "S_4") (pintype "passive"))
      (node (ref "U$22") (pin "2") (pinfunction "P$2_2") (pintype "bidirectional"))
    )
    (net (code "47") (name "Net-(K1B-O)") (class "Default")
      (node (ref "K1") (pin "9") (pinfunction "O_9") (pintype "passive"))
      (node (ref "VCC_RELAIS_100") (pin "1") (pinfunction "1_1") (pintype "passive"))
    )
    (net (code "48") (name "Net-(K1B-P)") (class "Default")
      (node (ref "K1") (pin "8") (pinfunction "P_8") (pintype "passive"))
      (node (ref "U$21") (pin "1") (pinfunction "P$1_1") (pintype "bidirectional"))
    )
    (net (code "49") (name "Net-(K1B-S)") (class "Default")
      (node (ref "K1") (pin "7") (pinfunction "S_7") (pintype "passive"))
      (node (ref "U$21") (pin "2") (pinfunction "P$2_2") (pintype "bidirectional"))
    )
    (net (code "50") (name "Net-(K2A-O)") (class "Default")
      (node (ref "K2") (pin "2") (pinfunction "O_2") (pintype "passive"))
      (node (ref "VCC_RELAIS_103") (pin "1") (pinfunction "1_1") (pintype "passive"))
    )
    (net (code "51") (name "Net-(K2A-P)") (class "Default")
      (node (ref "K2") (pin "3") (pinfunction "P_3") (pintype "passive"))
      (node (ref "U$24") (pin "1") (pinfunction "P$1_1") (pintype "bidirectional"))
    )
    (net (code "52") (name "Net-(K2A-S)") (class "Default")
      (node (ref "K2") (pin "4") (pinfunction "S_4") (pintype "passive"))
      (node (ref "U$24") (pin "2") (pinfunction "P$2_2") (pintype "bidirectional"))
    )
    (net (code "53") (name "Net-(K2B-O)") (class "Default")
      (node (ref "K2") (pin "9") (pinfunction "O_9") (pintype "passive"))
      (node (ref "VCC_RELAIS_102") (pin "2") (pinfunction "2_2") (pintype "passive"))
    )
    (net (code "54") (name "Net-(K2B-P)") (class "Default")
      (node (ref "K2") (pin "8") (pinfunction "P_8") (pintype "passive"))
      (node (ref "U$23") (pin "1") (pinfunction "P$1_1") (pintype "bidirectional"))
    )
    (net (code "55") (name "Net-(K2B-S)") (class "Default")
      (node (ref "K2") (pin "7") (pinfunction "S_7") (pintype "passive"))
      (node (ref "U$23") (pin "2") (pinfunction "P$2_2") (pintype "bidirectional"))
    )
    (net (code "56") (name "Net-(LED-C)") (class "Default")
      (node (ref "LED") (pin "K") (pinfunction "C_K") (pintype "passive"))
      (node (ref "U$2") (pin "1") (pinfunction "STAT_1") (pintype "output"))
    )
    (net (code "57") (name "Net-(LED-PadA)") (class "Default")
      (node (ref "LED") (pin "A") (pinfunction "A_A") (pintype "passive"))
      (node (ref "R2") (pin "2") (pinfunction "2_2") (pintype "passive"))
    )
    (net (code "58") (name "Net-(U$1-2)") (class "Default")
      (node (ref "U$1") (pin "P$2") (pinfunction "2_P$2") (pintype "passive"))
      (node (ref "U1") (pin "1") (pinfunction "SW_1") (pintype "output"))
    )
    (net (code "59") (name "Net-(U$2-PROG)") (class "Default")
      (node (ref "R1") (pin "1") (pinfunction "1_1") (pintype "passive"))
      (node (ref "U$2") (pin "5") (pinfunction "PROG_5") (pintype "input"))
    )
    (net (code "60") (name "Net-(U1-FB)") (class "Default")
      (node (ref "R6") (pin "2") (pinfunction "2_2") (pintype "passive"))
      (node (ref "R7") (pin "1") (pinfunction "1_1") (pintype "passive"))
      (node (ref "U1") (pin "4") (pinfunction "FB_4") (pintype "input"))
    )
    (net (code "61") (name "VCC") (class "Default")
      (node (ref "C6") (pin "1") (pinfunction "1_1") (pintype "passive"))
      (node (ref "LOAD_SUPPLY") (pin "2") (pinfunction "2_2") (pintype "passive"))
      (node (ref "RELAY_SUPPLY") (pin "1") (pinfunction "1_1") (pintype "passive"))
      (node (ref "VCC") (pin "1") (pinfunction "P$1_1") (pintype "bidirectional"))
      (node (ref "VCC_RELAIS_100") (pin "2") (pinfunction "2_2") (pintype "passive"))
      (node (ref "VCC_RELAIS_101") (pin "2") (pinfunction "2_2") (pintype "passive"))
      (node (ref "VCC_RELAIS_102") (pin "1") (pinfunction "1_1") (pintype "passive"))
      (node (ref "VCC_RELAIS_103") (pin "2") (pinfunction "2_2") (pintype "passive"))
    )
    (net (code "62") (name "unconnected-(1_RFM12-PadNFFS{slash}OOK)") (class "Default")
      (node (ref "1_RFM12") (pin "NFFS/OOK") (pinfunction "NFFS/OOK_NFFS/OOK") (pintype "bidirectional"))
    )
    (net (code "63") (name "unconnected-(1_RFM69-PadDIO2{slash}OOK)") (class "Default")
      (node (ref "1_RFM69") (pin "DIO2/OOK") (pinfunction "DIO2/OOK_DIO2/OOK") (pintype "open_collector"))
    )
    (net (code "64") (name "unconnected-(FTDI-Pad2)") (class "Default")
      (node (ref "FTDI") (pin "2") (pinfunction "2_2") (pintype "passive"))
    )
    (net (code "65") (name "unconnected-(IC2-I6-Pad6)") (class "Default")
      (node (ref "IC2") (pin "6") (pinfunction "I6_6") (pintype "input"))
    )
    (net (code "66") (name "unconnected-(IC2-I7-Pad7)") (class "Default")
      (node (ref "IC2") (pin "7") (pinfunction "I7_7") (pintype "input"))
    )
    (net (code "67") (name "unconnected-(IC2-O6-Pad11)") (class "Default")
      (node (ref "IC2") (pin "11") (pinfunction "O6_11") (pintype "open_collector"))
    )
    (net (code "68") (name "unconnected-(IC2-O7-Pad10)") (class "Default")
      (node (ref "IC2") (pin "10") (pinfunction "O7_10") (pintype "open_collector"))
    )
    (net (code "69") (name "unconnected-(U$3-P$1-Pad1)") (class "Default")
      (node (ref "U$3") (pin "1") (pinfunction "P$1_1") (pintype "bidirectional"))
    )
    (net (code "70") (name "unconnected-(U$3-P$2-Pad2)") (class "Default")
      (node (ref "U$3") (pin "2") (pinfunction "P$2_2") (pintype "bidirectional"))
    )
    (net (code "71") (name "unconnected-(U$5-P$1-Pad1)") (class "Default")
      (node (ref "U$5") (pin "1") (pinfunction "P$1_1") (pintype "bidirectional"))
    )
    (net (code "72") (name "unconnected-(U$5-P$2-Pad2)") (class "Default")
      (node (ref "U$5") (pin "2") (pinfunction "P$2_2") (pintype "bidirectional"))
    )
    (net (code "73") (name "unconnected-(U$6-P$1-Pad1)") (class "Default")
      (node (ref "U$6") (pin "1") (pinfunction "P$1_1") (pintype "bidirectional"))
    )
    (net (code "74") (name "unconnected-(U$6-P$2-Pad2)") (class "Default")
      (node (ref "U$6") (pin "2") (pinfunction "P$2_2") (pintype "bidirectional"))
    )
    (net (code "75") (name "unconnected-(U$7-P$1-Pad1)") (class "Default")
      (node (ref "U$7") (pin "1") (pinfunction "P$1_1") (pintype "bidirectional"))
    )
    (net (code "76") (name "unconnected-(U$7-P$2-Pad2)") (class "Default")
      (node (ref "U$7") (pin "2") (pinfunction "P$2_2") (pintype "bidirectional"))
    )
    (net (code "77") (name "unconnected-(U$8-P$1-Pad1)") (class "Default")
      (node (ref "U$8") (pin "1") (pinfunction "P$1_1") (pintype "bidirectional"))
    )
    (net (code "78") (name "unconnected-(U$8-P$2-Pad2)") (class "Default")
      (node (ref "U$8") (pin "2") (pinfunction "P$2_2") (pintype "bidirectional"))
    )
    (net (code "79") (name "unconnected-(U$9-P$1-Pad1)") (class "Default")
      (node (ref "U$9") (pin "1") (pinfunction "P$1_1") (pintype "bidirectional"))
    )
    (net (code "80") (name "unconnected-(U$9-P$2-Pad2)") (class "Default")
      (node (ref "U$9") (pin "2") (pinfunction "P$2_2") (pintype "bidirectional"))
    )
    (net (code "81") (name "unconnected-(U$10-P$1-Pad1)") (class "Default")
      (node (ref "U$10") (pin "1") (pinfunction "P$1_1") (pintype "bidirectional"))
    )
    (net (code "82") (name "unconnected-(U$10-P$2-Pad2)") (class "Default")
      (node (ref "U$10") (pin "2") (pinfunction "P$2_2") (pintype "bidirectional"))
    )
    (net (code "83") (name "unconnected-(U$11-WP-Pad3_WP)") (class "Default")
      (node (ref "U$11") (pin "3_WP") (pinfunction "WP_3_WP") (pintype "bidirectional"))
    )
    (net (code "84") (name "unconnected-(U$12-P$1-Pad1)") (class "Default")
      (node (ref "U$12") (pin "1") (pinfunction "P$1_1") (pintype "bidirectional"))
    )
    (net (code "85") (name "unconnected-(U$12-P$2-Pad2)") (class "Default")
      (node (ref "U$12") (pin "2") (pinfunction "P$2_2") (pintype "bidirectional"))
    )
    (net (code "86") (name "unconnected-(U$13-P$1-Pad1)") (class "Default")
      (node (ref "U$13") (pin "1") (pinfunction "P$1_1") (pintype "bidirectional"))
    )
    (net (code "87") (name "unconnected-(U$13-P$2-Pad2)") (class "Default")
      (node (ref "U$13") (pin "2") (pinfunction "P$2_2") (pintype "bidirectional"))
    )
    (net (code "88") (name "unconnected-(U$14-P$1-Pad1)") (class "Default")
      (node (ref "U$14") (pin "1") (pinfunction "P$1_1") (pintype "bidirectional"))
    )
    (net (code "89") (name "unconnected-(U$14-P$2-Pad2)") (class "Default")
      (node (ref "U$14") (pin "2") (pinfunction "P$2_2") (pintype "bidirectional"))
    )
    (net (code "90") (name "unconnected-(U$15-P$1-Pad1)") (class "Default")
      (node (ref "U$15") (pin "1") (pinfunction "P$1_1") (pintype "bidirectional"))
    )
    (net (code "91") (name "unconnected-(U$15-P$2-Pad2)") (class "Default")
      (node (ref "U$15") (pin "2") (pinfunction "P$2_2") (pintype "bidirectional"))
    )
    (net (code "92") (name "unconnected-(U$16-P$1-Pad1)") (class "Default")
      (node (ref "U$16") (pin "1") (pinfunction "P$1_1") (pintype "bidirectional"))
    )
    (net (code "93") (name "unconnected-(U$16-P$2-Pad2)") (class "Default")
      (node (ref "U$16") (pin "2") (pinfunction "P$2_2") (pintype "bidirectional"))
    )
    (net (code "94") (name "unconnected-(U$17-P$1-Pad1)") (class "Default")
      (node (ref "U$17") (pin "1") (pinfunction "P$1_1") (pintype "bidirectional"))
    )
    (net (code "95") (name "unconnected-(U$17-P$2-Pad2)") (class "Default")
      (node (ref "U$17") (pin "2") (pinfunction "P$2_2") (pintype "bidirectional"))
    )
    (net (code "96") (name "unconnected-(U$19-P$1-Pad1)") (class "Default")
      (node (ref "U$19") (pin "1") (pinfunction "P$1_1") (pintype "bidirectional"))
    )
    (net (code "97") (name "unconnected-(U$19-P$2-Pad2)") (class "Default")
      (node (ref "U$19") (pin "2") (pinfunction "P$2_2") (pintype "bidirectional"))
    )
    (net (code "98") (name "unconnected-(U$20-P$1-Pad1)") (class "Default")
      (node (ref "U$20") (pin "1") (pinfunction "P$1_1") (pintype "bidirectional"))
    )
    (net (code "99") (name "unconnected-(U$20-P$2-Pad2)") (class "Default")
      (node (ref "U$20") (pin "2") (pinfunction "P$2_2") (pintype "bidirectional"))
    )
    (net (code "100") (name "unconnected-(U$25-P$1-Pad1)") (class "Default")
      (node (ref "U$25") (pin "1") (pinfunction "P$1_1") (pintype "bidirectional"))
    )
    (net (code "101") (name "unconnected-(U$25-P$2-Pad2)") (class "Default")
      (node (ref "U$25") (pin "2") (pinfunction "P$2_2") (pintype "bidirectional"))
    )
    (net (code "102") (name "unconnected-(U$26-P$1-Pad1)") (class "Default")
      (node (ref "U$26") (pin "1") (pinfunction "P$1_1") (pintype "bidirectional"))
    )
    (net (code "103") (name "unconnected-(U$26-P$2-Pad2)") (class "Default")
      (node (ref "U$26") (pin "2") (pinfunction "P$2_2") (pintype "bidirectional"))
    )
    (net (code "104") (name "unconnected-(U$29-P$1-Pad1)") (class "Default")
      (node (ref "U$29") (pin "1") (pinfunction "P$1_1") (pintype "bidirectional"))
    )
    (net (code "105") (name "unconnected-(U$29-P$2-Pad2)") (class "Default")
      (node (ref "U$29") (pin "2") (pinfunction "P$2_2") (pintype "bidirectional"))
    )
    (net (code "106") (name "unconnected-(U$30-P$1-Pad1)") (class "Default")
      (node (ref "U$30") (pin "1") (pinfunction "P$1_1") (pintype "bidirectional"))
    )
    (net (code "107") (name "unconnected-(U$30-P$2-Pad2)") (class "Default")
      (node (ref "U$30") (pin "2") (pinfunction "P$2_2") (pintype "bidirectional"))
    )
    (net (code "108") (name "unconnected-(USB-PadD+)") (class "Default")
      (node (ref "USB") (pin "D+") (pinfunction "D+_D+") (pintype "bidirectional"))
    )
    (net (code "109") (name "unconnected-(USB-PadD-)") (class "Default")
      (node (ref "USB") (pin "D-") (pinfunction "D-_D-") (pintype "bidirectional"))
    )
    (net (code "110") (name "unconnected-(USB-PadID)") (class "Default")
      (node (ref "USB") (pin "ID") (pinfunction "ID_ID") (pintype "bidirectional"))
    )
  )
)
